# td2_cpu_r00.net
KiCad netlist of a schematic drawn in Altium Designer
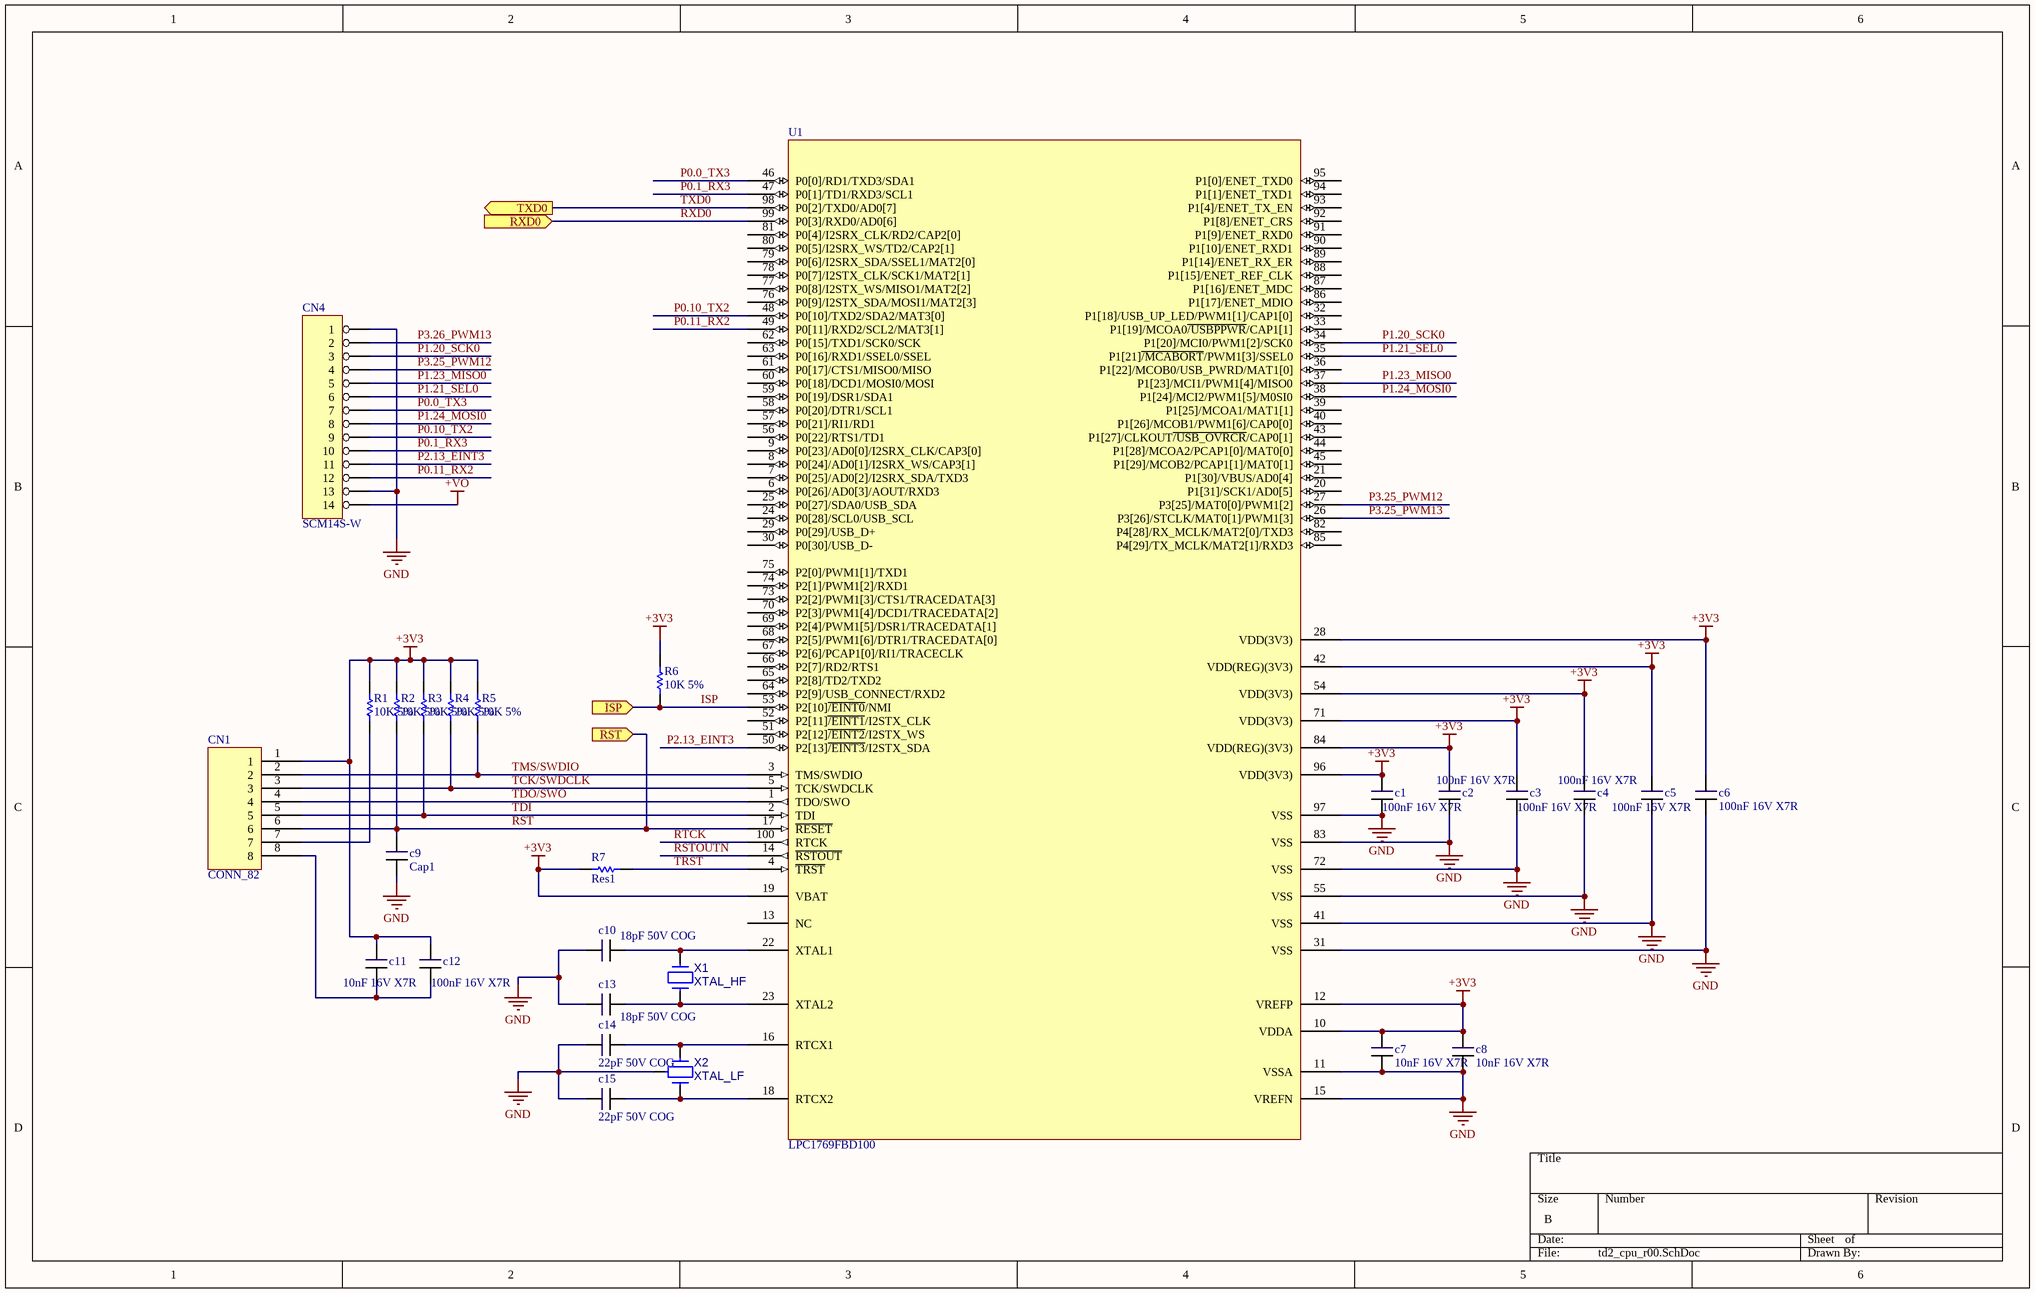
[diagram p0: td2_cpu_r00.SchDoc]

(export (version "E")
  (design (tool "Eeschema 10.0.6"))
  (components
    (comp (ref "c1")
      (value "100nF 16V X7R")
      (description "Capacitor")
      (libsource (lib "TDII_Lib") (part "Cap1"))
    )
    (comp (ref "c2")
      (value "100nF 16V X7R")
      (description "Capacitor")
      (libsource (lib "TDII_Lib") (part "Cap1"))
    )
    (comp (ref "c3")
      (value "100nF 16V X7R")
      (description "Capacitor")
      (libsource (lib "TDII_Lib") (part "Cap1"))
    )
    (comp (ref "c4")
      (value "100nF 16V X7R")
      (description "Capacitor")
      (libsource (lib "TDII_Lib") (part "Cap1"))
    )
    (comp (ref "c5")
      (value "100nF 16V X7R")
      (description "Capacitor")
      (libsource (lib "TDII_Lib") (part "Cap1"))
    )
    (comp (ref "c6")
      (value "100nF 16V X7R")
      (description "Capacitor")
      (libsource (lib "TDII_Lib") (part "Cap1"))
    )
    (comp (ref "c7")
      (value "10nF 16V X7R")
      (description "Capacitor")
      (libsource (lib "TDII_Lib") (part "Cap1"))
    )
    (comp (ref "c8")
      (value "10nF 16V X7R")
      (description "Capacitor")
      (libsource (lib "TDII_Lib") (part "Cap1"))
    )
    (comp (ref "c9") (value "Cap1") (description "Capacitor") (libsource (lib "TDII_Lib") (part "Cap1")))
    (comp (ref "c10")
      (value "18pF 50V COG")
      (description "Capacitor")
      (libsource (lib "TDII_Lib") (part "Cap1"))
    )
    (comp (ref "c11")
      (value "10nF 16V X7R")
      (description "Capacitor")
      (libsource (lib "TDII_Lib") (part "Cap1"))
    )
    (comp (ref "c12")
      (value "100nF 16V X7R")
      (description "Capacitor")
      (libsource (lib "TDII_Lib") (part "Cap1"))
    )
    (comp (ref "c13")
      (value "18pF 50V COG")
      (description "Capacitor")
      (libsource (lib "TDII_Lib") (part "Cap1"))
    )
    (comp (ref "c14")
      (value "22pF 50V COG")
      (description "Capacitor")
      (libsource (lib "TDII_Lib") (part "Cap1"))
    )
    (comp (ref "c15")
      (value "22pF 50V COG")
      (description "Capacitor")
      (libsource (lib "TDII_Lib") (part "Cap1"))
    )
    (comp (ref "CN1") (value "CONN_82") (libsource (lib "TDII_Lib") (part "CONN_82")))
    (comp (ref "CN4")
      (value "SCM14S-W")
      (description "Connector 14 Vias")
      (libsource (lib "TDII_Lib_V2") (part "CONN_14P"))
    )
    (comp (ref "R1") (value "10K 5%") (description "Resistor") (libsource (lib "TDII_Lib") (part "Res1")))
    (comp (ref "R2") (value "10K 5%") (description "Resistor") (libsource (lib "TDII_Lib") (part "Res1")))
    (comp (ref "R3") (value "10K 5%") (description "Resistor") (libsource (lib "TDII_Lib") (part "Res1")))
    (comp (ref "R4") (value "10K 5%") (description "Resistor") (libsource (lib "TDII_Lib") (part "Res1")))
    (comp (ref "R5") (value "10K 5%") (description "Resistor") (libsource (lib "TDII_Lib") (part "Res1")))
    (comp (ref "R6") (value "10K 5%") (description "Resistor") (libsource (lib "TDII_Lib") (part "Res1")))
    (comp (ref "R7") (value "Res1") (description "Resistor") (libsource (lib "TDII_Lib") (part "Res1")))
    (comp (ref "U1")
      (value "LPC1769FBD100")
      (footprint "LQFP100")
      (description "CPU Cortex M3")
      (libsource (lib "TDII_Lib_V2") (part "LPC1768FBD100"))
    )
    (comp (ref "X1") (value "XTAL_HF") (description "Crystal") (libsource (lib "TDII_Lib") (part "XTAL_HF")))
    (comp (ref "X2") (value "XTAL_LF") (description "Crystal") (libsource (lib "TDII_Lib") (part "XTAL_LF")))
  )
  (nets
    (net (code "1") (name "+3V3") (class "Default")
      (node (ref "CN1") (pin "1") (pinfunction "1_1") (pintype "passive"))
      (node (ref "R1") (pin "2") (pinfunction "2_2") (pintype "passive"))
      (node (ref "R2") (pin "2") (pinfunction "2_2") (pintype "passive"))
      (node (ref "R3") (pin "2") (pinfunction "2_2") (pintype "passive"))
      (node (ref "R4") (pin "2") (pinfunction "2_2") (pintype "passive"))
      (node (ref "R5") (pin "2") (pinfunction "2_2") (pintype "passive"))
      (node (ref "R6") (pin "1") (pinfunction "1_1") (pintype "passive"))
      (node (ref "R7") (pin "2") (pinfunction "2_2") (pintype "passive"))
      (node (ref "U1") (pin "10") (pinfunction "VDDA_10") (pintype "power_in"))
      (node (ref "U1") (pin "12") (pinfunction "VREFP_12") (pintype "power_in"))
      (node (ref "U1") (pin "19") (pinfunction "VBAT_19") (pintype "power_in"))
      (node (ref "U1") (pin "28") (pinfunction "VDD(3V3)_28") (pintype "power_in"))
      (node (ref "U1") (pin "42") (pinfunction "VDD(REG)(3V3)_42") (pintype "power_in"))
      (node (ref "U1") (pin "54") (pinfunction "VDD(3V3)_54") (pintype "power_in"))
      (node (ref "U1") (pin "71") (pinfunction "VDD(3V3)_71") (pintype "power_in"))
      (node (ref "U1") (pin "84") (pinfunction "VDD(REG)(3V3)_84") (pintype "power_in"))
      (node (ref "U1") (pin "96") (pinfunction "VDD(3V3)_96") (pintype "power_in"))
      (node (ref "c1") (pin "2") (pinfunction "2_2") (pintype "passive"))
      (node (ref "c11") (pin "2") (pinfunction "2_2") (pintype "passive"))
      (node (ref "c12") (pin "2") (pinfunction "2_2") (pintype "passive"))
      (node (ref "c2") (pin "2") (pinfunction "2_2") (pintype "passive"))
      (node (ref "c3") (pin "2") (pinfunction "2_2") (pintype "passive"))
      (node (ref "c4") (pin "2") (pinfunction "2_2") (pintype "passive"))
      (node (ref "c5") (pin "2") (pinfunction "2_2") (pintype "passive"))
      (node (ref "c6") (pin "2") (pinfunction "2_2") (pintype "passive"))
      (node (ref "c7") (pin "2") (pinfunction "2_2") (pintype "passive"))
      (node (ref "c8") (pin "2") (pinfunction "2_2") (pintype "passive"))
    )
    (net (code "2") (name "+VO") (class "Default")
      (node (ref "CN4") (pin "14") (pinfunction "14_14") (pintype "passive"))
    )
    (net (code "3") (name "/ISP") (class "Default")
      (node (ref "R6") (pin "2") (pinfunction "2_2") (pintype "passive"))
      (node (ref "U1") (pin "53") (pinfunction "P2[10]~{/EINT0}/NMI_53") (pintype "bidirectional"))
    )
    (net (code "4") (name "/P0.0_TX3") (class "Default")
      (node (ref "CN4") (pin "7") (pinfunction "7_7") (pintype "passive"))
      (node (ref "U1") (pin "46") (pinfunction "P0[0]/RD1/TXD3/SDA1_46") (pintype "bidirectional"))
    )
    (net (code "5") (name "/P0.1_RX3") (class "Default")
      (node (ref "CN4") (pin "10") (pinfunction "10_10") (pintype "passive"))
      (node (ref "U1") (pin "47") (pinfunction "P0[1]/TD1/RXD3/SCL1_47") (pintype "bidirectional"))
    )
    (net (code "6") (name "/P0.10_TX2") (class "Default")
      (node (ref "CN4") (pin "9") (pinfunction "9_9") (pintype "passive"))
      (node (ref "U1") (pin "48") (pinfunction "P0[10]/TXD2/SDA2/MAT3[0]_48") (pintype "bidirectional"))
    )
    (net (code "7") (name "/P0.11_RX2") (class "Default")
      (node (ref "CN4") (pin "12") (pinfunction "12_12") (pintype "passive"))
      (node (ref "U1") (pin "49") (pinfunction "P0[11]/RXD2/SCL2/MAT3[1]_49") (pintype "bidirectional"))
    )
    (net (code "8") (name "/P1.20_SCK0") (class "Default")
      (node (ref "CN4") (pin "3") (pinfunction "3_3") (pintype "passive"))
      (node (ref "U1") (pin "34") (pinfunction "P1[20]/MCI0/PWM1[2]/SCK0_34") (pintype "bidirectional"))
    )
    (net (code "9") (name "/P1.21_SEL0") (class "Default")
      (node (ref "CN4") (pin "6") (pinfunction "6_6") (pintype "passive"))
      (node (ref "U1") (pin "35") (pinfunction "P1[21]~{/MCABORT}/PWM1[3]/SSEL0_35") (pintype "bidirectional"))
    )
    (net (code "10") (name "/P1.23_MISO0") (class "Default")
      (node (ref "CN4") (pin "5") (pinfunction "5_5") (pintype "passive"))
      (node (ref "U1") (pin "37") (pinfunction "P1[23]/MCI1/PWM1[4]/MISO0_37") (pintype "bidirectional"))
    )
    (net (code "11") (name "/P1.24_MOSI0") (class "Default")
      (node (ref "CN4") (pin "8") (pinfunction "8_8") (pintype "passive"))
      (node (ref "U1") (pin "38") (pinfunction "P1[24]/MCI2/PWM1[5]/M0SI0_38") (pintype "bidirectional"))
    )
    (net (code "12") (name "/P2.13_EINT3") (class "Default")
      (node (ref "CN4") (pin "11") (pinfunction "11_11") (pintype "passive"))
      (node (ref "U1") (pin "50") (pinfunction "P2[13]~{/EINT3}/I2STX_SDA_50") (pintype "bidirectional"))
    )
    (net (code "13") (name "/P3.25_PWM12") (class "Default")
      (node (ref "CN4") (pin "4") (pinfunction "4_4") (pintype "passive"))
      (node (ref "U1") (pin "27") (pinfunction "P3[25]/MAT0[0]/PWM1[2]_27") (pintype "bidirectional"))
    )
    (net (code "14") (name "/P3.25_PWM13") (class "Default")
      (node (ref "U1") (pin "26") (pinfunction "P3[26]/STCLK/MAT0[1]/PWM1[3]_26") (pintype "bidirectional"))
    )
    (net (code "15") (name "/P3.26_PWM13") (class "Default")
      (node (ref "CN4") (pin "2") (pinfunction "2_2") (pintype "passive"))
    )
    (net (code "16") (name "/RST") (class "Default")
      (node (ref "CN1") (pin "6") (pinfunction "6_6") (pintype "passive"))
      (node (ref "R2") (pin "1") (pinfunction "1_1") (pintype "passive"))
      (node (ref "U1") (pin "17") (pinfunction "~{RESET}_17") (pintype "input"))
      (node (ref "c9") (pin "2") (pinfunction "2_2") (pintype "passive"))
    )
    (net (code "17") (name "/RSTOUTN") (class "Default")
      (node (ref "U1") (pin "14") (pinfunction "~{RSTOUT}_14") (pintype "output"))
    )
    (net (code "18") (name "/RTCK") (class "Default")
      (node (ref "U1") (pin "100") (pinfunction "RTCK_100") (pintype "output"))
    )
    (net (code "19") (name "/RXD0") (class "Default")
      (node (ref "U1") (pin "99") (pinfunction "P0[3]/RXD0/AD0[6]_99") (pintype "bidirectional"))
    )
    (net (code "20") (name "/TCK{slash}SWDCLK") (class "Default")
      (node (ref "CN1") (pin "3") (pinfunction "3_3") (pintype "passive"))
      (node (ref "R4") (pin "1") (pinfunction "1_1") (pintype "passive"))
      (node (ref "U1") (pin "5") (pinfunction "TCK/SWDCLK_5") (pintype "input"))
    )
    (net (code "21") (name "/TDI") (class "Default")
      (node (ref "CN1") (pin "5") (pinfunction "5_5") (pintype "passive"))
      (node (ref "R3") (pin "1") (pinfunction "1_1") (pintype "passive"))
      (node (ref "U1") (pin "2") (pinfunction "TDI_2") (pintype "input"))
    )
    (net (code "22") (name "/TDO{slash}SWO") (class "Default")
      (node (ref "CN1") (pin "4") (pinfunction "4_4") (pintype "passive"))
      (node (ref "U1") (pin "1") (pinfunction "TDO/SWO_1") (pintype "output"))
    )
    (net (code "23") (name "/TMS{slash}SWDIO") (class "Default")
      (node (ref "CN1") (pin "2") (pinfunction "2_2") (pintype "passive"))
      (node (ref "R5") (pin "1") (pinfunction "1_1") (pintype "passive"))
      (node (ref "U1") (pin "3") (pinfunction "TMS/SWDIO_3") (pintype "input"))
    )
    (net (code "24") (name "/TRST") (class "Default")
      (node (ref "R7") (pin "1") (pinfunction "1_1") (pintype "passive"))
      (node (ref "U1") (pin "4") (pinfunction "~{TRST}_4") (pintype "input"))
    )
    (net (code "25") (name "/TXD0") (class "Default")
      (node (ref "U1") (pin "98") (pinfunction "P0[2]/TXD0/AD0[7]_98") (pintype "bidirectional"))
    )
    (net (code "26") (name "GND") (class "Default")
      (node (ref "CN4") (pin "1") (pinfunction "1_1") (pintype "passive"))
      (node (ref "CN4") (pin "13") (pinfunction "13_13") (pintype "passive"))
      (node (ref "U1") (pin "11") (pinfunction "VSSA_11") (pintype "power_in"))
      (node (ref "U1") (pin "15") (pinfunction "VREFN_15") (pintype "power_in"))
      (node (ref "U1") (pin "31") (pinfunction "VSS_31") (pintype "power_in"))
      (node (ref "U1") (pin "41") (pinfunction "VSS_41") (pintype "power_in"))
      (node (ref "U1") (pin "55") (pinfunction "VSS_55") (pintype "power_in"))
      (node (ref "U1") (pin "72") (pinfunction "VSS_72") (pintype "power_in"))
      (node (ref "U1") (pin "83") (pinfunction "VSS_83") (pintype "power_in"))
      (node (ref "U1") (pin "97") (pinfunction "VSS_97") (pintype "power_in"))
      (node (ref "X2") (pin "3") (pinfunction "3_3") (pintype "passive"))
      (node (ref "c1") (pin "1") (pinfunction "tutu_1") (pintype "passive"))
      (node (ref "c10") (pin "2") (pinfunction "2_2") (pintype "passive"))
      (node (ref "c13") (pin "2") (pinfunction "2_2") (pintype "passive"))
      (node (ref "c14") (pin "2") (pinfunction "2_2") (pintype "passive"))
      (node (ref "c15") (pin "2") (pinfunction "2_2") (pintype "passive"))
      (node (ref "c2") (pin "1") (pinfunction "tutu_1") (pintype "passive"))
      (node (ref "c3") (pin "1") (pinfunction "tutu_1") (pintype "passive"))
      (node (ref "c4") (pin "1") (pinfunction "tutu_1") (pintype "passive"))
      (node (ref "c5") (pin "1") (pinfunction "tutu_1") (pintype "passive"))
      (node (ref "c6") (pin "1") (pinfunction "tutu_1") (pintype "passive"))
      (node (ref "c7") (pin "1") (pinfunction "tutu_1") (pintype "passive"))
      (node (ref "c8") (pin "1") (pinfunction "tutu_1") (pintype "passive"))
      (node (ref "c9") (pin "1") (pinfunction "tutu_1") (pintype "passive"))
    )
    (net (code "27") (name "Net-(CN1-Pad7)") (class "Default")
      (node (ref "CN1") (pin "7") (pinfunction "7_7") (pintype "passive"))
      (node (ref "R1") (pin "1") (pinfunction "1_1") (pintype "passive"))
    )
    (net (code "28") (name "Net-(U1-RTCX1)") (class "Default")
      (node (ref "U1") (pin "16") (pinfunction "RTCX1_16") (pintype "passive"))
      (node (ref "X2") (pin "2") (pinfunction "2_2") (pintype "passive"))
      (node (ref "c14") (pin "1") (pinfunction "tutu_1") (pintype "passive"))
    )
    (net (code "29") (name "Net-(U1-RTCX2)") (class "Default")
      (node (ref "U1") (pin "18") (pinfunction "RTCX2_18") (pintype "passive"))
      (node (ref "X2") (pin "1") (pinfunction "1_1") (pintype "passive"))
      (node (ref "c15") (pin "1") (pinfunction "tutu_1") (pintype "passive"))
    )
    (net (code "30") (name "Net-(U1-XTAL1)") (class "Default")
      (node (ref "U1") (pin "22") (pinfunction "XTAL1_22") (pintype "passive"))
      (node (ref "X1") (pin "1") (pinfunction "1_1") (pintype "passive"))
      (node (ref "c10") (pin "1") (pinfunction "tutu_1") (pintype "passive"))
    )
    (net (code "31") (name "Net-(U1-XTAL2)") (class "Default")
      (node (ref "U1") (pin "23") (pinfunction "XTAL2_23") (pintype "passive"))
      (node (ref "X1") (pin "2") (pinfunction "2_2") (pintype "passive"))
      (node (ref "c13") (pin "1") (pinfunction "tutu_1") (pintype "passive"))
    )
    (net (code "32") (name "Net-(c11-tutu)") (class "Default")
      (node (ref "CN1") (pin "8") (pinfunction "8_8") (pintype "passive"))
      (node (ref "c11") (pin "1") (pinfunction "tutu_1") (pintype "passive"))
      (node (ref "c12") (pin "1") (pinfunction "tutu_1") (pintype "passive"))
    )
    (net (code "33") (name "unconnected-(U1-NC-Pad13)") (class "Default")
      (node (ref "U1") (pin "13") (pinfunction "NC_13") (pintype "passive"))
    )
    (net (code "34") (name "unconnected-(U1-P0[4]{slash}I2SRX_CLK{slash}RD2{slash}CAP2[0]-Pad81)") (class "Default")
      (node (ref "U1") (pin "81") (pinfunction "P0[4]/I2SRX_CLK/RD2/CAP2[0]_81") (pintype "bidirectional"))
    )
    (net (code "35") (name "unconnected-(U1-P0[5]{slash}I2SRX_WS{slash}TD2{slash}CAP2[1]-Pad80)") (class "Default")
      (node (ref "U1") (pin "80") (pinfunction "P0[5]/I2SRX_WS/TD2/CAP2[1]_80") (pintype "bidirectional"))
    )
    (net (code "36") (name "unconnected-(U1-P0[6]{slash}I2SRX_SDA{slash}SSEL1{slash}MAT2[0]-Pad79)") (class "Default")
      (node (ref "U1") (pin "79") (pinfunction "P0[6]/I2SRX_SDA/SSEL1/MAT2[0]_79") (pintype "bidirectional"))
    )
    (net (code "37") (name "unconnected-(U1-P0[7]{slash}I2STX_CLK{slash}SCK1{slash}MAT2[1]-Pad78)") (class "Default")
      (node (ref "U1") (pin "78") (pinfunction "P0[7]/I2STX_CLK/SCK1/MAT2[1]_78") (pintype "bidirectional"))
    )
    (net (code "38") (name "unconnected-(U1-P0[8]{slash}I2STX_WS{slash}MISO1{slash}MAT2[2]-Pad77)") (class "Default")
      (node (ref "U1") (pin "77") (pinfunction "P0[8]/I2STX_WS/MISO1/MAT2[2]_77") (pintype "bidirectional"))
    )
    (net (code "39") (name "unconnected-(U1-P0[9]{slash}I2STX_SDA{slash}MOSI1{slash}MAT2[3]-Pad76)") (class "Default")
      (node (ref "U1") (pin "76") (pinfunction "P0[9]/I2STX_SDA/MOSI1/MAT2[3]_76") (pintype "bidirectional"))
    )
    (net (code "40") (name "unconnected-(U1-P0[15]{slash}TXD1{slash}SCK0{slash}SCK-Pad62)") (class "Default")
      (node (ref "U1") (pin "62") (pinfunction "P0[15]/TXD1/SCK0/SCK_62") (pintype "bidirectional"))
    )
    (net (code "41") (name "unconnected-(U1-P0[16]{slash}RXD1{slash}SSEL0{slash}SSEL-Pad63)") (class "Default")
      (node (ref "U1") (pin "63") (pinfunction "P0[16]/RXD1/SSEL0/SSEL_63") (pintype "bidirectional"))
    )
    (net (code "42") (name "unconnected-(U1-P0[17]{slash}CTS1{slash}MISO0{slash}MISO-Pad61)") (class "Default")
      (node (ref "U1") (pin "61") (pinfunction "P0[17]/CTS1/MISO0/MISO_61") (pintype "bidirectional"))
    )
    (net (code "43") (name "unconnected-(U1-P0[18]{slash}DCD1{slash}MOSI0{slash}MOSI-Pad60)") (class "Default")
      (node (ref "U1") (pin "60") (pinfunction "P0[18]/DCD1/MOSI0/MOSI_60") (pintype "bidirectional"))
    )
    (net (code "44") (name "unconnected-(U1-P0[19]{slash}DSR1{slash}SDA1-Pad59)") (class "Default")
      (node (ref "U1") (pin "59") (pinfunction "P0[19]/DSR1/SDA1_59") (pintype "bidirectional"))
    )
    (net (code "45") (name "unconnected-(U1-P0[20]{slash}DTR1{slash}SCL1-Pad58)") (class "Default")
      (node (ref "U1") (pin "58") (pinfunction "P0[20]/DTR1/SCL1_58") (pintype "bidirectional"))
    )
    (net (code "46") (name "unconnected-(U1-P0[21]{slash}RI1{slash}RD1-Pad57)") (class "Default")
      (node (ref "U1") (pin "57") (pinfunction "P0[21]/RI1/RD1_57") (pintype "bidirectional"))
    )
    (net (code "47") (name "unconnected-(U1-P0[22]{slash}RTS1{slash}TD1-Pad56)") (class "Default")
      (node (ref "U1") (pin "56") (pinfunction "P0[22]/RTS1/TD1_56") (pintype "bidirectional"))
    )
    (net (code "48") (name "unconnected-(U1-P0[23]{slash}AD0[0]{slash}I2SRX_CLK{slash}CAP3[0]-Pad9)") (class "Default")
      (node (ref "U1") (pin "9") (pinfunction "P0[23]/AD0[0]/I2SRX_CLK/CAP3[0]_9") (pintype "bidirectional"))
    )
    (net (code "49") (name "unconnected-(U1-P0[24]{slash}AD0[1]{slash}I2SRX_WS{slash}CAP3[1]-Pad8)") (class "Default")
      (node (ref "U1") (pin "8") (pinfunction "P0[24]/AD0[1]/I2SRX_WS/CAP3[1]_8") (pintype "bidirectional"))
    )
    (net (code "50") (name "unconnected-(U1-P0[25]{slash}AD0[2]{slash}I2SRX_SDA{slash}TXD3-Pad7)") (class "Default")
      (node (ref "U1") (pin "7") (pinfunction "P0[25]/AD0[2]/I2SRX_SDA/TXD3_7") (pintype "bidirectional"))
    )
    (net (code "51") (name "unconnected-(U1-P0[26]{slash}AD0[3]{slash}AOUT{slash}RXD3-Pad6)") (class "Default")
      (node (ref "U1") (pin "6") (pinfunction "P0[26]/AD0[3]/AOUT/RXD3_6") (pintype "bidirectional"))
    )
    (net (code "52") (name "unconnected-(U1-P0[27]{slash}SDA0{slash}USB_SDA-Pad25)") (class "Default")
      (node (ref "U1") (pin "25") (pinfunction "P0[27]/SDA0/USB_SDA_25") (pintype "bidirectional"))
    )
    (net (code "53") (name "unconnected-(U1-P0[28]{slash}SCL0{slash}USB_SCL-Pad24)") (class "Default")
      (node (ref "U1") (pin "24") (pinfunction "P0[28]/SCL0/USB_SCL_24") (pintype "bidirectional"))
    )
    (net (code "54") (name "unconnected-(U1-P0[29]{slash}USB_D+-Pad29)") (class "Default")
      (node (ref "U1") (pin "29") (pinfunction "P0[29]/USB_D+_29") (pintype "bidirectional"))
    )
    (net (code "55") (name "unconnected-(U1-P0[30]{slash}USB_D--Pad30)") (class "Default")
      (node (ref "U1") (pin "30") (pinfunction "P0[30]/USB_D-_30") (pintype "bidirectional"))
    )
    (net (code "56") (name "unconnected-(U1-P1[0]{slash}ENET_TXD0-Pad95)") (class "Default")
      (node (ref "U1") (pin "95") (pinfunction "P1[0]/ENET_TXD0_95") (pintype "bidirectional"))
    )
    (net (code "57") (name "unconnected-(U1-P1[1]{slash}ENET_TXD1-Pad94)") (class "Default")
      (node (ref "U1") (pin "94") (pinfunction "P1[1]/ENET_TXD1_94") (pintype "bidirectional"))
    )
    (net (code "58") (name "unconnected-(U1-P1[4]{slash}ENET_TX_EN-Pad93)") (class "Default")
      (node (ref "U1") (pin "93") (pinfunction "P1[4]/ENET_TX_EN_93") (pintype "bidirectional"))
    )
    (net (code "59") (name "unconnected-(U1-P1[8]{slash}ENET_CRS-Pad92)") (class "Default")
      (node (ref "U1") (pin "92") (pinfunction "P1[8]/ENET_CRS_92") (pintype "bidirectional"))
    )
    (net (code "60") (name "unconnected-(U1-P1[9]{slash}ENET_RXD0-Pad91)") (class "Default")
      (node (ref "U1") (pin "91") (pinfunction "P1[9]/ENET_RXD0_91") (pintype "bidirectional"))
    )
    (net (code "61") (name "unconnected-(U1-P1[10]{slash}ENET_RXD1-Pad90)") (class "Default")
      (node (ref "U1") (pin "90") (pinfunction "P1[10]/ENET_RXD1_90") (pintype "bidirectional"))
    )
    (net (code "62") (name "unconnected-(U1-P1[14]{slash}ENET_RX_ER-Pad89)") (class "Default")
      (node (ref "U1") (pin "89") (pinfunction "P1[14]/ENET_RX_ER_89") (pintype "bidirectional"))
    )
    (net (code "63") (name "unconnected-(U1-P1[15]{slash}ENET_REF_CLK-Pad88)") (class "Default")
      (node (ref "U1") (pin "88") (pinfunction "P1[15]/ENET_REF_CLK_88") (pintype "bidirectional"))
    )
    (net (code "64") (name "unconnected-(U1-P1[16]{slash}ENET_MDC-Pad87)") (class "Default")
      (node (ref "U1") (pin "87") (pinfunction "P1[16]/ENET_MDC_87") (pintype "bidirectional"))
    )
    (net (code "65") (name "unconnected-(U1-P1[17]{slash}ENET_MDIO-Pad86)") (class "Default")
      (node (ref "U1") (pin "86") (pinfunction "P1[17]/ENET_MDIO_86") (pintype "bidirectional"))
    )
    (net (code "66") (name "unconnected-(U1-P1[18]{slash}USB_UP_LED{slash}PWM1[1]{slash}CAP1[0]-Pad32)") (class "Default")
      (node (ref "U1") (pin "32") (pinfunction "P1[18]/USB_UP_LED/PWM1[1]/CAP1[0]_32") (pintype "bidirectional"))
    )
    (net (code "67") (name "unconnected-(U1-P1[19]{slash}MCOA0~{{slash}USBPPWR}{slash}CAP1[1]-Pad33)") (class "Default")
      (node (ref "U1") (pin "33") (pinfunction "P1[19]/MCOA0~{/USBPPWR}/CAP1[1]_33") (pintype "bidirectional"))
    )
    (net (code "68") (name "unconnected-(U1-P1[22]{slash}MCOB0{slash}USB_PWRD{slash}MAT1[0]-Pad36)") (class "Default")
      (node (ref "U1") (pin "36") (pinfunction "P1[22]/MCOB0/USB_PWRD/MAT1[0]_36") (pintype "bidirectional"))
    )
    (net (code "69") (name "unconnected-(U1-P1[25]{slash}MCOA1{slash}MAT1[1]-Pad39)") (class "Default")
      (node (ref "U1") (pin "39") (pinfunction "P1[25]/MCOA1/MAT1[1]_39") (pintype "bidirectional"))
    )
    (net (code "70") (name "unconnected-(U1-P1[26]{slash}MCOB1{slash}PWM1[6]{slash}CAP0[0]-Pad40)") (class "Default")
      (node (ref "U1") (pin "40") (pinfunction "P1[26]/MCOB1/PWM1[6]/CAP0[0]_40") (pintype "bidirectional"))
    )
    (net (code "71") (name "unconnected-(U1-P1[27]{slash}CLKOUT~{{slash}USB_OVRCR}{slash}CAP0[1]-Pad43)") (class "Default")
      (node (ref "U1") (pin "43") (pinfunction "P1[27]/CLKOUT~{/USB_OVRCR}/CAP0[1]_43") (pintype "bidirectional"))
    )
    (net (code "72") (name "unconnected-(U1-P1[28]{slash}MCOA2{slash}PCAP1[0]{slash}MAT0[0]-Pad44)") (class "Default")
      (node (ref "U1") (pin "44") (pinfunction "P1[28]/MCOA2/PCAP1[0]/MAT0[0]_44") (pintype "bidirectional"))
    )
    (net (code "73") (name "unconnected-(U1-P1[29]{slash}MCOB2{slash}PCAP1[1]{slash}MAT0[1]-Pad45)") (class "Default")
      (node (ref "U1") (pin "45") (pinfunction "P1[29]/MCOB2/PCAP1[1]/MAT0[1]_45") (pintype "bidirectional"))
    )
    (net (code "74") (name "unconnected-(U1-P1[30]{slash}VBUS{slash}AD0[4]-Pad21)") (class "Default")
      (node (ref "U1") (pin "21") (pinfunction "P1[30]/VBUS/AD0[4]_21") (pintype "bidirectional"))
    )
    (net (code "75") (name "unconnected-(U1-P1[31]{slash}SCK1{slash}AD0[5]-Pad20)") (class "Default")
      (node (ref "U1") (pin "20") (pinfunction "P1[31]/SCK1/AD0[5]_20") (pintype "bidirectional"))
    )
    (net (code "76") (name "unconnected-(U1-P2[0]{slash}PWM1[1]{slash}TXD1-Pad75)") (class "Default")
      (node (ref "U1") (pin "75") (pinfunction "P2[0]/PWM1[1]/TXD1_75") (pintype "bidirectional"))
    )
    (net (code "77") (name "unconnected-(U1-P2[1]{slash}PWM1[2]{slash}RXD1-Pad74)") (class "Default")
      (node (ref "U1") (pin "74") (pinfunction "P2[1]/PWM1[2]/RXD1_74") (pintype "bidirectional"))
    )
    (net (code "78") (name "unconnected-(U1-P2[2]{slash}PWM1[3]{slash}CTS1{slash}TRACEDATA[3]-Pad73)") (class "Default")
      (node (ref "U1") (pin "73") (pinfunction "P2[2]/PWM1[3]/CTS1/TRACEDATA[3]_73") (pintype "bidirectional"))
    )
    (net (code "79") (name "unconnected-(U1-P2[3]{slash}PWM1[4]{slash}DCD1{slash}TRACEDATA[2]-Pad70)") (class "Default")
      (node (ref "U1") (pin "70") (pinfunction "P2[3]/PWM1[4]/DCD1/TRACEDATA[2]_70") (pintype "bidirectional"))
    )
    (net (code "80") (name "unconnected-(U1-P2[4]{slash}PWM1[5]{slash}DSR1{slash}TRACEDATA[1]-Pad69)") (class "Default")
      (node (ref "U1") (pin "69") (pinfunction "P2[4]/PWM1[5]/DSR1/TRACEDATA[1]_69") (pintype "bidirectional"))
    )
    (net (code "81") (name "unconnected-(U1-P2[5]{slash}PWM1[6]{slash}DTR1{slash}TRACEDATA[0]-Pad68)") (class "Default")
      (node (ref "U1") (pin "68") (pinfunction "P2[5]/PWM1[6]/DTR1/TRACEDATA[0]_68") (pintype "bidirectional"))
    )
    (net (code "82") (name "unconnected-(U1-P2[6]{slash}PCAP1[0]{slash}RI1{slash}TRACECLK-Pad67)") (class "Default")
      (node (ref "U1") (pin "67") (pinfunction "P2[6]/PCAP1[0]/RI1/TRACECLK_67") (pintype "bidirectional"))
    )
    (net (code "83") (name "unconnected-(U1-P2[7]{slash}RD2{slash}RTS1-Pad66)") (class "Default")
      (node (ref "U1") (pin "66") (pinfunction "P2[7]/RD2/RTS1_66") (pintype "bidirectional"))
    )
    (net (code "84") (name "unconnected-(U1-P2[8]{slash}TD2{slash}TXD2-Pad65)") (class "Default")
      (node (ref "U1") (pin "65") (pinfunction "P2[8]/TD2/TXD2_65") (pintype "bidirectional"))
    )
    (net (code "85") (name "unconnected-(U1-P2[9]{slash}USB_CONNECT{slash}RXD2-Pad64)") (class "Default")
      (node (ref "U1") (pin "64") (pinfunction "P2[9]/USB_CONNECT/RXD2_64") (pintype "bidirectional"))
    )
    (net (code "86") (name "unconnected-(U1-P2[11]~{{slash}EINT1}{slash}I2STX_CLK-Pad52)") (class "Default")
      (node (ref "U1") (pin "52") (pinfunction "P2[11]~{/EINT1}/I2STX_CLK_52") (pintype "bidirectional"))
    )
    (net (code "87") (name "unconnected-(U1-P2[12]~{{slash}EINT2}{slash}I2STX_WS-Pad51)") (class "Default")
      (node (ref "U1") (pin "51") (pinfunction "P2[12]~{/EINT2}/I2STX_WS_51") (pintype "bidirectional"))
    )
    (net (code "88") (name "unconnected-(U1-P4[28]{slash}RX_MCLK{slash}MAT2[0]{slash}TXD3-Pad82)") (class "Default")
      (node (ref "U1") (pin "82") (pinfunction "P4[28]/RX_MCLK/MAT2[0]/TXD3_82") (pintype "bidirectional"))
    )
    (net (code "89") (name "unconnected-(U1-P4[29]{slash}TX_MCLK{slash}MAT2[1]{slash}RXD3-Pad85)") (class "Default")
      (node (ref "U1") (pin "85") (pinfunction "P4[29]/TX_MCLK/MAT2[1]/RXD3_85") (pintype "bidirectional"))
    )
  )
)
